# brunnen_v2.net
KiCad netlist of a schematic drawn in EAGLE
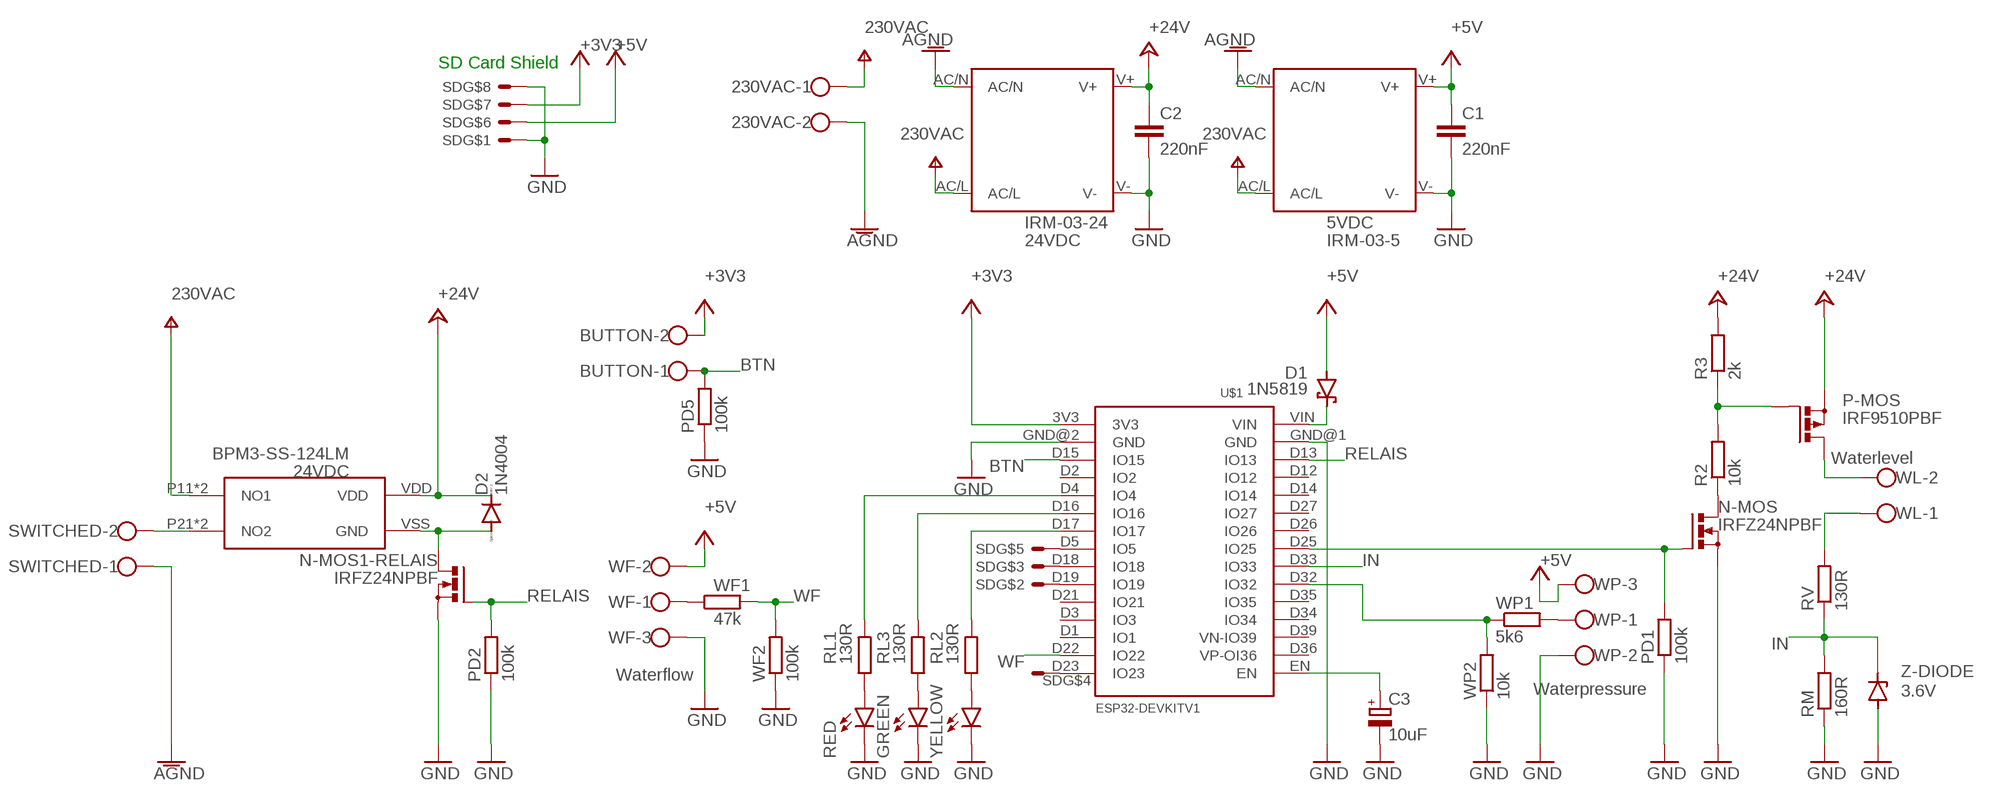
[diagram p0: schematic, sheet 1]

(export (version "E")
  (design (tool "Eeschema 10.0.6"))
  (components
    (comp (ref "230VAC")
      (value "W237-102")
      (footprint "eagle-import:W237-102")
      (fields (field (name "MPN") "237-102"))
      (libsource (lib "eagle-import") (part "W237-102"))
    )
    (comp (ref "BUTTON")
      (value "W237-102")
      (footprint "eagle-import:W237-102")
      (fields (field (name "MPN") "237-102"))
      (libsource (lib "eagle-import") (part "W237-102"))
    )
    (comp (ref "C1")
      (value "220nF")
      (footprint "eagle-import:C025-025X050")
      (libsource (lib "eagle-import") (part "C-EU025-025X050"))
    )
    (comp (ref "C2")
      (value "220nF")
      (footprint "eagle-import:C025-025X050")
      (libsource (lib "eagle-import") (part "C-EU025-025X050"))
    )
    (comp (ref "C3")
      (value "10uF")
      (footprint "eagle-import:E2-4")
      (libsource (lib "eagle-import") (part "CPOL-EUE2-4"))
    )
    (comp (ref "D1")
      (value "1N5819")
      (footprint "eagle-import:DO41-7.6")
      (libsource (lib "eagle-import") (part "1N5819-B"))
    )
    (comp (ref "D2")
      (value "1N4004")
      (footprint "eagle-import:DO41-10")
      (libsource (lib "eagle-import") (part "1N4004"))
    )
    (comp (ref "GREEN")
      (value "LED5MM")
      (footprint "eagle-import:LED5MM")
      (libsource (lib "eagle-import") (part "LED5MM"))
    )
    (comp (ref "IRM-03-5")
      (value "5VDC")
      (footprint "eagle-import:IRM_03")
      (libsource (lib "eagle-import") (part "IRM_03IRM_03"))
    )
    (comp (ref "IRM-03-24")
      (value "24VDC")
      (footprint "eagle-import:IRM_03")
      (libsource (lib "eagle-import") (part "IRM_03IRM_03"))
    )
    (comp (ref "N-MOS")
      (value "IRFZ24NPBF")
      (footprint "eagle-import:TO220BV")
      (libsource (lib "eagle-import") (part "PMOSFET_NTO220BV"))
    )
    (comp (ref "N-MOS1-RELAIS")
      (value "IRFZ24NPBF")
      (footprint "eagle-import:TO220BV")
      (libsource (lib "eagle-import") (part "PMOSFET_NTO220BV"))
    )
    (comp (ref "P-MOS")
      (value "IRF9510PBF")
      (footprint "eagle-import:TO220BV")
      (libsource (lib "eagle-import") (part "PMOSFET_PTO220BV"))
    )
    (comp (ref "PD1")
      (value "100k")
      (footprint "eagle-import:0207_10")
      (libsource (lib "eagle-import") (part "R-EU_0207/10"))
    )
    (comp (ref "PD2")
      (value "100k")
      (footprint "eagle-import:0207_10")
      (libsource (lib "eagle-import") (part "R-EU_0207/10"))
    )
    (comp (ref "PD5")
      (value "100k")
      (footprint "eagle-import:0207_10")
      (libsource (lib "eagle-import") (part "R-EU_0207/10"))
    )
    (comp (ref "R2")
      (value "10k")
      (footprint "eagle-import:0207_10")
      (libsource (lib "eagle-import") (part "R-EU_0207/10"))
    )
    (comp (ref "R3")
      (value "2k")
      (footprint "eagle-import:0207_10")
      (libsource (lib "eagle-import") (part "R-EU_0207/10"))
    )
    (comp (ref "RED")
      (value "LED5MM")
      (footprint "eagle-import:LED5MM")
      (libsource (lib "eagle-import") (part "LED5MM"))
    )
    (comp (ref "RL1")
      (value "130R")
      (footprint "eagle-import:0207_10")
      (libsource (lib "eagle-import") (part "R-EU_0207/10"))
    )
    (comp (ref "RL2")
      (value "130R")
      (footprint "eagle-import:0207_10")
      (libsource (lib "eagle-import") (part "R-EU_0207/10"))
    )
    (comp (ref "RL3")
      (value "130R")
      (footprint "eagle-import:0207_10")
      (libsource (lib "eagle-import") (part "R-EU_0207/10"))
    )
    (comp (ref "RM")
      (value "160R")
      (footprint "eagle-import:0207_10")
      (libsource (lib "eagle-import") (part "R-EU_0207/10"))
    )
    (comp (ref "RV")
      (value "130R")
      (footprint "eagle-import:0207_10")
      (libsource (lib "eagle-import") (part "R-EU_0207/10"))
    )
    (comp (ref "SD")
      (value "322-16-DUAL")
      (footprint "eagle-import:322-16-DUAL")
      (libsource (lib "eagle-import") (part "322-16-DUAL"))
    )
    (comp (ref "SWITCHED")
      (value "W237-102")
      (footprint "eagle-import:W237-102")
      (fields (field (name "MPN") "237-102"))
      (libsource (lib "eagle-import") (part "W237-102"))
    )
    (comp (ref "U$1")
      (value "ESP32DEVKITV1")
      (footprint "eagle-import:ESP32-DEVKITV1")
      (libsource (lib "eagle-import") (part "ESP32DEVKITV1"))
    )
    (comp (ref "U$2")
      (value "BPM3-SS-124LM")
      (footprint "eagle-import:BPM3-SS-124LM")
      (libsource (lib "eagle-import") (part "BPM3-SS-124LM"))
    )
    (comp (ref "WF")
      (value "Waterflow")
      (footprint "eagle-import:W237-103")
      (fields (field (name "MPN") "237-103"))
      (libsource (lib "eagle-import") (part "W237-103"))
    )
    (comp (ref "WF1")
      (value "47k")
      (footprint "eagle-import:0207_10")
      (libsource (lib "eagle-import") (part "R-EU_0207/10"))
    )
    (comp (ref "WF2")
      (value "100k")
      (footprint "eagle-import:0207_10")
      (libsource (lib "eagle-import") (part "R-EU_0207/10"))
    )
    (comp (ref "WL")
      (value "Waterlevel")
      (footprint "eagle-import:W237-102")
      (fields (field (name "MPN") "237-102"))
      (libsource (lib "eagle-import") (part "W237-102"))
    )
    (comp (ref "WP")
      (value "Waterpressure")
      (footprint "eagle-import:W237-103")
      (fields (field (name "MPN") "237-103"))
      (libsource (lib "eagle-import") (part "W237-103"))
    )
    (comp (ref "WP1")
      (value "5k6")
      (footprint "eagle-import:0207_10")
      (libsource (lib "eagle-import") (part "R-EU_0207/10"))
    )
    (comp (ref "WP2")
      (value "10k")
      (footprint "eagle-import:0207_10")
      (libsource (lib "eagle-import") (part "R-EU_0207/10"))
    )
    (comp (ref "YELLOW")
      (value "LED5MM")
      (footprint "eagle-import:LED5MM")
      (libsource (lib "eagle-import") (part "LED5MM"))
    )
    (comp (ref "Z-DIODE")
      (value "3.6V")
      (footprint "eagle-import:F126Z10")
      (libsource (lib "eagle-import") (part "ZENER-DIODEF126-10"))
    )
  )
  (nets
    (net (code "1") (name "+3V3") (class "Default")
      (node (ref "BUTTON") (pin "2") (pinfunction "KL_2") (pintype "passive"))
      (node (ref "SD") (pin "13") (pinfunction "S_13") (pintype "passive"))
      (node (ref "SD") (pin "14") (pinfunction "S_14") (pintype "passive"))
      (node (ref "U$1") (pin "3V3") (pinfunction "3V3_3V3") (pintype "bidirectional"))
    )
    (net (code "2") (name "+5V") (class "Default")
      (node (ref "C1") (pin "1") (pinfunction "1_1") (pintype "passive"))
      (node (ref "D1") (pin "A") (pinfunction "A_A") (pintype "passive"))
      (node (ref "IRM-03-5") (pin "V+") (pinfunction "V+_V+") (pintype "output"))
      (node (ref "SD") (pin "11") (pinfunction "S_11") (pintype "passive"))
      (node (ref "SD") (pin "12") (pinfunction "S_12") (pintype "passive"))
      (node (ref "WF") (pin "2") (pinfunction "KL_2") (pintype "passive"))
      (node (ref "WP") (pin "3") (pinfunction "KL_3") (pintype "passive"))
    )
    (net (code "3") (name "+24V") (class "Default")
      (node (ref "C2") (pin "1") (pinfunction "1_1") (pintype "passive"))
      (node (ref "D2") (pin "C") (pinfunction "C_C") (pintype "passive"))
      (node (ref "IRM-03-24") (pin "V+") (pinfunction "V+_V+") (pintype "output"))
      (node (ref "P-MOS") (pin "S") (pinfunction "S_S") (pintype "passive"))
      (node (ref "R3") (pin "2") (pinfunction "2_2") (pintype "passive"))
      (node (ref "U$2") (pin "VDD") (pinfunction "VDD_VDD") (pintype "bidirectional"))
    )
    (net (code "4") (name "/BTN") (class "Default")
      (node (ref "BUTTON") (pin "1") (pinfunction "KL_1") (pintype "passive"))
      (node (ref "PD5") (pin "2") (pinfunction "2_2") (pintype "passive"))
      (node (ref "U$1") (pin "D15") (pinfunction "IO15_D15") (pintype "bidirectional"))
    )
    (net (code "5") (name "/IN") (class "Default")
      (node (ref "RM") (pin "2") (pinfunction "2_2") (pintype "passive"))
      (node (ref "RV") (pin "1") (pinfunction "1_1") (pintype "passive"))
      (node (ref "U$1") (pin "D33") (pinfunction "IO33_D33") (pintype "bidirectional"))
      (node (ref "Z-DIODE") (pin "C") (pinfunction "C_C") (pintype "passive"))
    )
    (net (code "6") (name "/RELAIS") (class "Default")
      (node (ref "N-MOS1-RELAIS") (pin "G") (pinfunction "G_G") (pintype "passive"))
      (node (ref "PD2") (pin "2") (pinfunction "2_2") (pintype "passive"))
      (node (ref "U$1") (pin "D13") (pinfunction "IO13_D13") (pintype "bidirectional"))
    )
    (net (code "7") (name "/WF") (class "Default")
      (node (ref "U$1") (pin "D22") (pinfunction "IO22_D22") (pintype "bidirectional"))
      (node (ref "WF1") (pin "2") (pinfunction "2_2") (pintype "passive"))
      (node (ref "WF2") (pin "2") (pinfunction "2_2") (pintype "passive"))
    )
    (net (code "8") (name "230VAC") (class "Default")
      (node (ref "230VAC") (pin "1") (pinfunction "KL_1") (pintype "passive"))
      (node (ref "IRM-03-24") (pin "AC/L") (pinfunction "AC/L_AC/L") (pintype "input"))
      (node (ref "IRM-03-5") (pin "AC/L") (pinfunction "AC/L_AC/L") (pintype "input"))
      (node (ref "U$2") (pin "P11") (pinfunction "NO1_P11") (pintype "bidirectional"))
      (node (ref "U$2") (pin "P12") (pinfunction "NO1_P12") (pintype "bidirectional"))
    )
    (net (code "9") (name "AGND") (class "Default")
      (node (ref "230VAC") (pin "2") (pinfunction "KL_2") (pintype "passive"))
      (node (ref "IRM-03-24") (pin "AC/N") (pinfunction "AC/N_AC/N") (pintype "input"))
      (node (ref "IRM-03-5") (pin "AC/N") (pinfunction "AC/N_AC/N") (pintype "input"))
      (node (ref "SWITCHED") (pin "1") (pinfunction "KL_1") (pintype "passive"))
    )
    (net (code "10") (name "GND") (class "Default")
      (node (ref "C1") (pin "2") (pinfunction "2_2") (pintype "passive"))
      (node (ref "C2") (pin "2") (pinfunction "2_2") (pintype "passive"))
      (node (ref "C3") (pin "-") (pinfunction "-_-") (pintype "passive"))
      (node (ref "GREEN") (pin "K") (pinfunction "C_K") (pintype "passive"))
      (node (ref "IRM-03-24") (pin "V-") (pinfunction "V-_V-") (pintype "output"))
      (node (ref "IRM-03-5") (pin "V-") (pinfunction "V-_V-") (pintype "output"))
      (node (ref "N-MOS") (pin "S") (pinfunction "S_S") (pintype "passive"))
      (node (ref "N-MOS1-RELAIS") (pin "S") (pinfunction "S_S") (pintype "passive"))
      (node (ref "PD1") (pin "1") (pinfunction "1_1") (pintype "passive"))
      (node (ref "PD2") (pin "1") (pinfunction "1_1") (pintype "passive"))
      (node (ref "PD5") (pin "1") (pinfunction "1_1") (pintype "passive"))
      (node (ref "RED") (pin "K") (pinfunction "C_K") (pintype "passive"))
      (node (ref "RM") (pin "1") (pinfunction "1_1") (pintype "passive"))
      (node (ref "SD") (pin "1") (pinfunction "S_1") (pintype "passive"))
      (node (ref "SD") (pin "15") (pinfunction "S_15") (pintype "passive"))
      (node (ref "SD") (pin "16") (pinfunction "S_16") (pintype "passive"))
      (node (ref "SD") (pin "2") (pinfunction "S_2") (pintype "passive"))
      (node (ref "U$1") (pin "GND@1") (pinfunction "GND_GND@1") (pintype "bidirectional"))
      (node (ref "U$1") (pin "GND@2") (pinfunction "GND_GND@2") (pintype "bidirectional"))
      (node (ref "WF") (pin "3") (pinfunction "KL_3") (pintype "passive"))
      (node (ref "WF2") (pin "1") (pinfunction "1_1") (pintype "passive"))
      (node (ref "WP") (pin "2") (pinfunction "KL_2") (pintype "passive"))
      (node (ref "WP2") (pin "1") (pinfunction "1_1") (pintype "passive"))
      (node (ref "YELLOW") (pin "K") (pinfunction "C_K") (pintype "passive"))
      (node (ref "Z-DIODE") (pin "A") (pinfunction "A_A") (pintype "passive"))
    )
    (net (code "11") (name "Net-(C3-Pad+)") (class "Default")
      (node (ref "C3") (pin "+") (pinfunction "+_+") (pintype "passive"))
      (node (ref "U$1") (pin "EN") (pinfunction "EN_EN") (pintype "bidirectional"))
    )
    (net (code "12") (name "Net-(D1-PadC)") (class "Default")
      (node (ref "D1") (pin "C") (pinfunction "C_C") (pintype "passive"))
      (node (ref "U$1") (pin "VIN") (pinfunction "VIN_VIN") (pintype "bidirectional"))
    )
    (net (code "13") (name "Net-(GREEN-PadA)") (class "Default")
      (node (ref "GREEN") (pin "A") (pinfunction "A_A") (pintype "passive"))
      (node (ref "RL3") (pin "1") (pinfunction "1_1") (pintype "passive"))
    )
    (net (code "14") (name "Net-(N-MOS-PadD)") (class "Default")
      (node (ref "N-MOS") (pin "D") (pinfunction "D_D") (pintype "passive"))
      (node (ref "R2") (pin "1") (pinfunction "1_1") (pintype "passive"))
    )
    (net (code "15") (name "Net-(P-MOS-PadG)") (class "Default")
      (node (ref "P-MOS") (pin "G") (pinfunction "G_G") (pintype "passive"))
      (node (ref "R2") (pin "2") (pinfunction "2_2") (pintype "passive"))
      (node (ref "R3") (pin "1") (pinfunction "1_1") (pintype "passive"))
    )
    (net (code "16") (name "Net-(RED-PadA)") (class "Default")
      (node (ref "RED") (pin "A") (pinfunction "A_A") (pintype "passive"))
      (node (ref "RL1") (pin "1") (pinfunction "1_1") (pintype "passive"))
    )
    (net (code "17") (name "Net-(RL2-Pad1)") (class "Default")
      (node (ref "RL2") (pin "1") (pinfunction "1_1") (pintype "passive"))
      (node (ref "YELLOW") (pin "A") (pinfunction "A_A") (pintype "passive"))
    )
    (net (code "18") (name "Net-(SWITCHEDB-KL)") (class "Default")
      (node (ref "SWITCHED") (pin "2") (pinfunction "KL_2") (pintype "passive"))
      (node (ref "U$2") (pin "P21") (pinfunction "NO2_P21") (pintype "bidirectional"))
      (node (ref "U$2") (pin "P22") (pinfunction "NO2_P22") (pintype "bidirectional"))
    )
    (net (code "19") (name "Net-(U$1-IO4)") (class "Default")
      (node (ref "RL1") (pin "2") (pinfunction "2_2") (pintype "passive"))
      (node (ref "U$1") (pin "D4") (pinfunction "IO4_D4") (pintype "bidirectional"))
    )
    (net (code "20") (name "Net-(U$1-IO5)") (class "Default")
      (node (ref "SD") (pin "10") (pinfunction "S_10") (pintype "passive"))
      (node (ref "SD") (pin "9") (pinfunction "S_9") (pintype "passive"))
      (node (ref "U$1") (pin "D5") (pinfunction "IO5_D5") (pintype "bidirectional"))
    )
    (net (code "21") (name "Net-(U$1-IO16)") (class "Default")
      (node (ref "RL3") (pin "2") (pinfunction "2_2") (pintype "passive"))
      (node (ref "U$1") (pin "D16") (pinfunction "IO16_D16") (pintype "bidirectional"))
    )
    (net (code "22") (name "Net-(U$1-IO17)") (class "Default")
      (node (ref "RL2") (pin "2") (pinfunction "2_2") (pintype "passive"))
      (node (ref "U$1") (pin "D17") (pinfunction "IO17_D17") (pintype "bidirectional"))
    )
    (net (code "23") (name "Net-(U$1-IO18)") (class "Default")
      (node (ref "SD") (pin "5") (pinfunction "S_5") (pintype "passive"))
      (node (ref "SD") (pin "6") (pinfunction "S_6") (pintype "passive"))
      (node (ref "U$1") (pin "D18") (pinfunction "IO18_D18") (pintype "bidirectional"))
    )
    (net (code "24") (name "Net-(U$1-IO19)") (class "Default")
      (node (ref "SD") (pin "3") (pinfunction "S_3") (pintype "passive"))
      (node (ref "SD") (pin "4") (pinfunction "S_4") (pintype "passive"))
      (node (ref "U$1") (pin "D19") (pinfunction "IO19_D19") (pintype "bidirectional"))
    )
    (net (code "25") (name "Net-(U$1-IO23)") (class "Default")
      (node (ref "SD") (pin "7") (pinfunction "S_7") (pintype "passive"))
      (node (ref "SD") (pin "8") (pinfunction "S_8") (pintype "passive"))
      (node (ref "U$1") (pin "D23") (pinfunction "IO23_D23") (pintype "bidirectional"))
    )
    (net (code "26") (name "Net-(U$1-IO25)") (class "Default")
      (node (ref "N-MOS") (pin "G") (pinfunction "G_G") (pintype "passive"))
      (node (ref "PD1") (pin "2") (pinfunction "2_2") (pintype "passive"))
      (node (ref "U$1") (pin "D25") (pinfunction "IO25_D25") (pintype "bidirectional"))
    )
    (net (code "27") (name "Net-(U$1-IO32)") (class "Default")
      (node (ref "U$1") (pin "D32") (pinfunction "IO32_D32") (pintype "bidirectional"))
      (node (ref "WP1") (pin "1") (pinfunction "1_1") (pintype "passive"))
      (node (ref "WP2") (pin "2") (pinfunction "2_2") (pintype "passive"))
    )
    (net (code "28") (name "Net-(U$2-GND)") (class "Default")
      (node (ref "D2") (pin "A") (pinfunction "A_A") (pintype "passive"))
      (node (ref "N-MOS1-RELAIS") (pin "D") (pinfunction "D_D") (pintype "passive"))
      (node (ref "U$2") (pin "VSS") (pinfunction "GND_VSS") (pintype "bidirectional"))
    )
    (net (code "29") (name "Net-(WFA-KL)") (class "Default")
      (node (ref "WF") (pin "1") (pinfunction "KL_1") (pintype "passive"))
      (node (ref "WF1") (pin "1") (pinfunction "1_1") (pintype "passive"))
    )
    (net (code "30") (name "Net-(WLA-KL)") (class "Default")
      (node (ref "RV") (pin "2") (pinfunction "2_2") (pintype "passive"))
      (node (ref "WL") (pin "1") (pinfunction "KL_1") (pintype "passive"))
    )
    (net (code "31") (name "Net-(WLB-KL)") (class "Default")
      (node (ref "P-MOS") (pin "D") (pinfunction "D_D") (pintype "passive"))
      (node (ref "WL") (pin "2") (pinfunction "KL_2") (pintype "passive"))
    )
    (net (code "32") (name "Net-(WPA-KL)") (class "Default")
      (node (ref "WP") (pin "1") (pinfunction "KL_1") (pintype "passive"))
      (node (ref "WP1") (pin "2") (pinfunction "2_2") (pintype "passive"))
    )
    (net (code "33") (name "unconnected-(U$1-IO1-PadD1)") (class "Default")
      (node (ref "U$1") (pin "D1") (pinfunction "IO1_D1") (pintype "bidirectional"))
    )
    (net (code "34") (name "unconnected-(U$1-IO2-PadD2)") (class "Default")
      (node (ref "U$1") (pin "D2") (pinfunction "IO2_D2") (pintype "bidirectional"))
    )
    (net (code "35") (name "unconnected-(U$1-IO3-PadD3)") (class "Default")
      (node (ref "U$1") (pin "D3") (pinfunction "IO3_D3") (pintype "bidirectional"))
    )
    (net (code "36") (name "unconnected-(U$1-IO12-PadD12)") (class "Default")
      (node (ref "U$1") (pin "D12") (pinfunction "IO12_D12") (pintype "bidirectional"))
    )
    (net (code "37") (name "unconnected-(U$1-IO14-PadD14)") (class "Default")
      (node (ref "U$1") (pin "D14") (pinfunction "IO14_D14") (pintype "bidirectional"))
    )
    (net (code "38") (name "unconnected-(U$1-IO21-PadD21)") (class "Default")
      (node (ref "U$1") (pin "D21") (pinfunction "IO21_D21") (pintype "bidirectional"))
    )
    (net (code "39") (name "unconnected-(U$1-IO26-PadD26)") (class "Default")
      (node (ref "U$1") (pin "D26") (pinfunction "IO26_D26") (pintype "bidirectional"))
    )
    (net (code "40") (name "unconnected-(U$1-IO27-PadD27)") (class "Default")
      (node (ref "U$1") (pin "D27") (pinfunction "IO27_D27") (pintype "bidirectional"))
    )
    (net (code "41") (name "unconnected-(U$1-IO34-PadD34)") (class "Default")
      (node (ref "U$1") (pin "D34") (pinfunction "IO34_D34") (pintype "bidirectional"))
    )
    (net (code "42") (name "unconnected-(U$1-IO35-PadD35)") (class "Default")
      (node (ref "U$1") (pin "D35") (pinfunction "IO35_D35") (pintype "bidirectional"))
    )
    (net (code "43") (name "unconnected-(U$1-VN-IO39-PadD39)") (class "Default")
      (node (ref "U$1") (pin "D39") (pinfunction "VN-IO39_D39") (pintype "bidirectional"))
    )
    (net (code "44") (name "unconnected-(U$1-VP-OI36-PadD36)") (class "Default")
      (node (ref "U$1") (pin "D36") (pinfunction "VP-OI36_D36") (pintype "bidirectional"))
    )
  )
)
